# bleumaus-nrf52832-mk-1_0_0.net
KiCad netlist of a schematic drawn in EAGLE
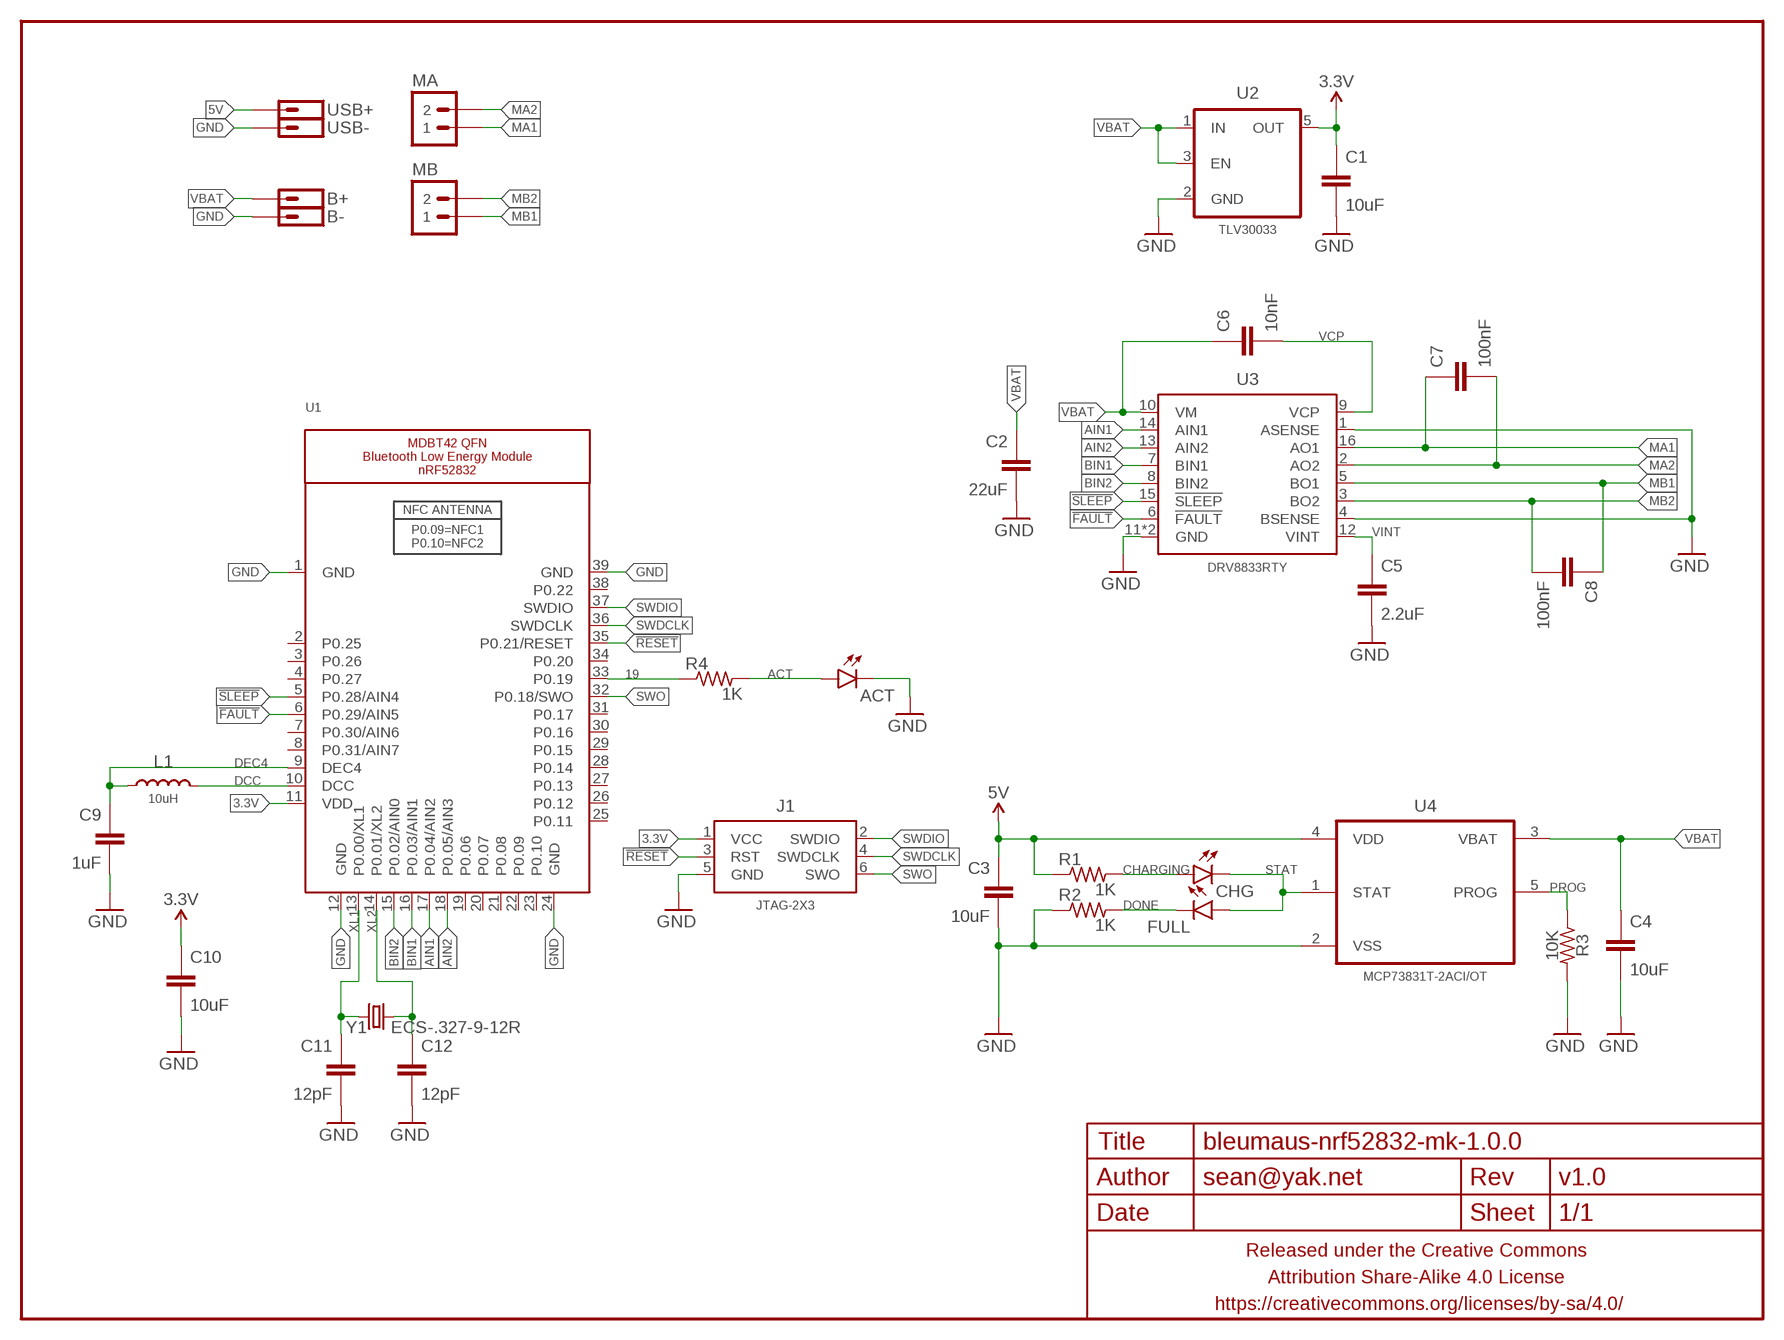
[diagram p0: schematic, sheet 1]

(export (version "E")
  (design (tool "Eeschema 10.0.6"))
  (components
    (comp (ref "ACT")
      (value "LED0603-TIGHT")
      (footprint "eagle-import:LED-0603-TIGHT")
      (libsource (lib "eagle-import") (part "LED0603-TIGHT"))
    )
    (comp (ref "B+")
      (value "M01SMD-1DIA")
      (footprint "eagle-import:1X01-SMD-1MM-DIA")
      (libsource (lib "eagle-import") (part "M01SMD-1DIA"))
    )
    (comp (ref "B-")
      (value "M01SMD-1DIA")
      (footprint "eagle-import:1X01-SMD-1MM-DIA")
      (libsource (lib "eagle-import") (part "M01SMD-1DIA"))
    )
    (comp (ref "C1")
      (value "10uF")
      (footprint "eagle-import:C0402")
      (libsource (lib "eagle-import") (part "CAPACITOR-CERAMICC0402"))
    )
    (comp (ref "C2")
      (value "22uF")
      (footprint "eagle-import:C1206")
      (libsource (lib "eagle-import") (part "CAPACITOR-CERAMICC1206"))
    )
    (comp (ref "C3")
      (value "10uF")
      (footprint "eagle-import:C0402")
      (libsource (lib "eagle-import") (part "CAPACITOR-CERAMICC0402"))
    )
    (comp (ref "C4")
      (value "10uF")
      (footprint "eagle-import:C0402")
      (libsource (lib "eagle-import") (part "CAPACITOR-CERAMICC0402"))
    )
    (comp (ref "C5")
      (value "2.2uF")
      (footprint "eagle-import:C0402")
      (libsource (lib "eagle-import") (part "CAPACITOR-CERAMICC0402"))
    )
    (comp (ref "C6")
      (value "10nF")
      (footprint "eagle-import:C0402")
      (libsource (lib "eagle-import") (part "CAPACITOR-CERAMICC0402"))
    )
    (comp (ref "C7")
      (value "100nF")
      (footprint "eagle-import:C0402")
      (libsource (lib "eagle-import") (part "CAPACITOR-CERAMICC0402"))
    )
    (comp (ref "C8")
      (value "100nF")
      (footprint "eagle-import:C0402")
      (libsource (lib "eagle-import") (part "CAPACITOR-CERAMICC0402"))
    )
    (comp (ref "C9")
      (value "1uF")
      (footprint "eagle-import:C0402")
      (libsource (lib "eagle-import") (part "CAPACITOR-CERAMICC0402"))
    )
    (comp (ref "C10")
      (value "10uF")
      (footprint "eagle-import:C0603-TIGHTER")
      (libsource (lib "eagle-import") (part "CAPACITOR-CERAMICC0603-TIGHTER"))
    )
    (comp (ref "C11")
      (value "12pF")
      (footprint "eagle-import:C0402")
      (libsource (lib "eagle-import") (part "CAPACITOR-CERAMICC0402"))
    )
    (comp (ref "C12")
      (value "12pF")
      (footprint "eagle-import:C0402")
      (libsource (lib "eagle-import") (part "CAPACITOR-CERAMICC0402"))
    )
    (comp (ref "CHG")
      (value "LED0603-TIGHT")
      (footprint "eagle-import:LED-0603-TIGHT")
      (libsource (lib "eagle-import") (part "LED0603-TIGHT"))
    )
    (comp (ref "FRAME1")
      (value "FRAME-LETTERNO_PACKAGE")
      (footprint "eagle-import:DUMMY")
      (fields
        (field (name "DESIGNER") "sean@yak.net")
        (field (name "VERSION") "v1.0")
        (field (name "DESIGNER_1") "sean@yak.net")
        (field (name "VERSION_1") "v1.0")
      )
      (libsource (lib "eagle-import") (part "FRAME-LETTERNO_PACKAGE"))
    )
    (comp (ref "FULL")
      (value "LED0603-TIGHT")
      (footprint "eagle-import:LED-0603-TIGHT")
      (libsource (lib "eagle-import") (part "LED0603-TIGHT"))
    )
    (comp (ref "J1")
      (value "JTAG-2X3")
      (footprint "eagle-import:2X3-1.27MM-SMD")
      (libsource (lib "eagle-import") (part "JTAG-2X3"))
    )
    (comp (ref "L1")
      (value "10uH")
      (footprint "eagle-import:0603")
      (libsource (lib "eagle-import") (part "INDUCTOR0603"))
    )
    (comp (ref "MA")
      (value "M02PTH-2MM")
      (footprint "eagle-import:1X02-2MM-PTH")
      (libsource (lib "eagle-import") (part "M02PTH-2MM"))
    )
    (comp (ref "MB")
      (value "M02PTH-2MM")
      (footprint "eagle-import:1X02-2MM-PTH")
      (libsource (lib "eagle-import") (part "M02PTH-2MM"))
    )
    (comp (ref "R1")
      (value "1K")
      (footprint "eagle-import:R0402")
      (libsource (lib "eagle-import") (part "RESISTORR0402"))
    )
    (comp (ref "R2")
      (value "1K")
      (footprint "eagle-import:R0402")
      (libsource (lib "eagle-import") (part "RESISTORR0402"))
    )
    (comp (ref "R3")
      (value "10K")
      (footprint "eagle-import:R0402")
      (libsource (lib "eagle-import") (part "RESISTORR0402"))
    )
    (comp (ref "R4")
      (value "1K")
      (footprint "eagle-import:R0402")
      (libsource (lib "eagle-import") (part "RESISTORR0402"))
    )
    (comp (ref "U1")
      (value "NRF52832_MODULE_MDBT42_NO2324")
      (footprint "eagle-import:BLE_MODULE_RAYTAC_MDBT42_NO2324")
      (libsource (lib "eagle-import") (part "NRF52832_MODULE_MDBT42_NO2324"))
    )
    (comp (ref "U2")
      (value "TLV30033")
      (footprint "eagle-import:SC70-TIGHTER")
      (libsource (lib "eagle-import") (part "V_REG_ENTLV700XXDCK-TIGHTER"))
    )
    (comp (ref "U3")
      (value "DRV8833RTY")
      (footprint "eagle-import:PWQFN-16")
      (libsource (lib "eagle-import") (part "DRV8833RTY"))
    )
    (comp (ref "U4")
      (value "MCP73831T-2ACI/OT")
      (footprint "eagle-import:SOT95P280X145-5N")
      (libsource (lib "eagle-import") (part "MCP73831T-2ACI/OT"))
    )
    (comp (ref "USB+")
      (value "M01SMD-1DIA")
      (footprint "eagle-import:1X01-SMD-1MM-DIA")
      (libsource (lib "eagle-import") (part "M01SMD-1DIA"))
    )
    (comp (ref "USB-")
      (value "M01SMD-1DIA")
      (footprint "eagle-import:1X01-SMD-1MM-DIA")
      (libsource (lib "eagle-import") (part "M01SMD-1DIA"))
    )
    (comp (ref "Y1")
      (value "ECS-.327-9-12R")
      (footprint "eagle-import:CRYSTAL-2X1.2MM")
      (libsource (lib "eagle-import") (part "CRYSTAL2X1.2MM"))
    )
  )
  (nets
    (net (code "1") (name "/19") (class "Default")
      (node (ref "R4") (pin "1") (pinfunction "1_1") (pintype "passive"))
      (node (ref "U1") (pin "33") (pinfunction "P0.19_33") (pintype "bidirectional"))
    )
    (net (code "2") (name "/ACT") (class "Default")
      (node (ref "ACT") (pin "A") (pinfunction "A_A") (pintype "passive"))
      (node (ref "R4") (pin "2") (pinfunction "2_2") (pintype "passive"))
    )
    (net (code "3") (name "/CHARGING") (class "Default")
      (node (ref "CHG") (pin "A") (pinfunction "A_A") (pintype "passive"))
      (node (ref "R1") (pin "2") (pinfunction "2_2") (pintype "passive"))
    )
    (net (code "4") (name "/DCC") (class "Default")
      (node (ref "L1") (pin "2") (pinfunction "2_2") (pintype "passive"))
      (node (ref "U1") (pin "10") (pinfunction "DCC_10") (pintype "bidirectional"))
    )
    (net (code "5") (name "/DEC4") (class "Default")
      (node (ref "C9") (pin "1") (pinfunction "1_1") (pintype "passive"))
      (node (ref "L1") (pin "1") (pinfunction "1_1") (pintype "passive"))
      (node (ref "U1") (pin "9") (pinfunction "DEC4_9") (pintype "bidirectional"))
    )
    (net (code "6") (name "/DONE") (class "Default")
      (node (ref "FULL") (pin "C") (pinfunction "C_C") (pintype "passive"))
      (node (ref "R2") (pin "2") (pinfunction "2_2") (pintype "passive"))
    )
    (net (code "7") (name "/PROG") (class "Default")
      (node (ref "R3") (pin "1") (pinfunction "1_1") (pintype "passive"))
      (node (ref "U4") (pin "5") (pinfunction "PROG_5") (pintype "input"))
    )
    (net (code "8") (name "/STAT") (class "Default")
      (node (ref "CHG") (pin "C") (pinfunction "C_C") (pintype "passive"))
      (node (ref "FULL") (pin "A") (pinfunction "A_A") (pintype "passive"))
      (node (ref "U4") (pin "1") (pinfunction "STAT_1") (pintype "output"))
    )
    (net (code "9") (name "/VCP") (class "Default")
      (node (ref "C6") (pin "2") (pinfunction "2_2") (pintype "passive"))
      (node (ref "U3") (pin "9") (pinfunction "VCP_9") (pintype "bidirectional"))
    )
    (net (code "10") (name "/VINT") (class "Default")
      (node (ref "C5") (pin "1") (pinfunction "1_1") (pintype "passive"))
      (node (ref "U3") (pin "12") (pinfunction "VINT_12") (pintype "bidirectional"))
    )
    (net (code "11") (name "/XL1") (class "Default")
      (node (ref "C11") (pin "1") (pinfunction "1_1") (pintype "passive"))
      (node (ref "U1") (pin "13") (pinfunction "P0.00/XL1_13") (pintype "bidirectional"))
      (node (ref "Y1") (pin "1") (pinfunction "1_1") (pintype "passive"))
    )
    (net (code "12") (name "/XL2") (class "Default")
      (node (ref "C12") (pin "1") (pinfunction "1_1") (pintype "passive"))
      (node (ref "U1") (pin "14") (pinfunction "P0.01/XL2_14") (pintype "bidirectional"))
      (node (ref "Y1") (pin "2") (pinfunction "2_2") (pintype "passive"))
    )
    (net (code "13") (name "/~{FAULT}") (class "Default")
      (node (ref "U1") (pin "6") (pinfunction "P0.29/AIN5_6") (pintype "bidirectional"))
      (node (ref "U3") (pin "6") (pinfunction "~{FAULT}_6") (pintype "output"))
    )
    (net (code "14") (name "/~{RESET}") (class "Default")
      (node (ref "J1") (pin "3") (pinfunction "RST_3") (pintype "bidirectional"))
      (node (ref "U1") (pin "35") (pinfunction "P0.21/RESET_35") (pintype "bidirectional"))
    )
    (net (code "15") (name "/~{SLEEP}") (class "Default")
      (node (ref "U1") (pin "5") (pinfunction "P0.28/AIN4_5") (pintype "bidirectional"))
      (node (ref "U3") (pin "15") (pinfunction "~{SLEEP}_15") (pintype "input"))
    )
    (net (code "16") (name "3.3V") (class "Default")
      (node (ref "C1") (pin "1") (pinfunction "1_1") (pintype "passive"))
      (node (ref "C10") (pin "1") (pinfunction "1_1") (pintype "passive"))
      (node (ref "J1") (pin "1") (pinfunction "VCC_1") (pintype "bidirectional"))
      (node (ref "U1") (pin "11") (pinfunction "VDD_11") (pintype "bidirectional"))
      (node (ref "U2") (pin "5") (pinfunction "OUT_5") (pintype "passive"))
    )
    (net (code "17") (name "5V") (class "Default")
      (node (ref "C3") (pin "1") (pinfunction "1_1") (pintype "passive"))
      (node (ref "R1") (pin "1") (pinfunction "1_1") (pintype "passive"))
      (node (ref "U4") (pin "4") (pinfunction "VDD_4") (pintype "power_in"))
      (node (ref "USB+") (pin "P$1") (pinfunction "1_P$1") (pintype "passive"))
    )
    (net (code "18") (name "AIN1") (class "Default")
      (node (ref "U1") (pin "17") (pinfunction "P0.04/AIN2_17") (pintype "bidirectional"))
      (node (ref "U3") (pin "14") (pinfunction "AIN1_14") (pintype "input"))
    )
    (net (code "19") (name "AIN2") (class "Default")
      (node (ref "U1") (pin "18") (pinfunction "P0.05/AIN3_18") (pintype "bidirectional"))
      (node (ref "U3") (pin "13") (pinfunction "AIN2_13") (pintype "input"))
    )
    (net (code "20") (name "BIN1") (class "Default")
      (node (ref "U1") (pin "16") (pinfunction "P0.03/AIN1_16") (pintype "bidirectional"))
      (node (ref "U3") (pin "7") (pinfunction "BIN1_7") (pintype "input"))
    )
    (net (code "21") (name "BIN2") (class "Default")
      (node (ref "U1") (pin "15") (pinfunction "P0.02/AIN0_15") (pintype "bidirectional"))
      (node (ref "U3") (pin "8") (pinfunction "BIN2_8") (pintype "input"))
    )
    (net (code "22") (name "GND") (class "Default")
      (node (ref "ACT") (pin "C") (pinfunction "C_C") (pintype "passive"))
      (node (ref "B-") (pin "P$1") (pinfunction "1_P$1") (pintype "passive"))
      (node (ref "C1") (pin "2") (pinfunction "2_2") (pintype "passive"))
      (node (ref "C10") (pin "2") (pinfunction "2_2") (pintype "passive"))
      (node (ref "C11") (pin "2") (pinfunction "2_2") (pintype "passive"))
      (node (ref "C12") (pin "2") (pinfunction "2_2") (pintype "passive"))
      (node (ref "C2") (pin "2") (pinfunction "2_2") (pintype "passive"))
      (node (ref "C3") (pin "2") (pinfunction "2_2") (pintype "passive"))
      (node (ref "C4") (pin "2") (pinfunction "2_2") (pintype "passive"))
      (node (ref "C5") (pin "2") (pinfunction "2_2") (pintype "passive"))
      (node (ref "C9") (pin "2") (pinfunction "2_2") (pintype "passive"))
      (node (ref "J1") (pin "5") (pinfunction "GND_5") (pintype "bidirectional"))
      (node (ref "R2") (pin "1") (pinfunction "1_1") (pintype "passive"))
      (node (ref "R3") (pin "2") (pinfunction "2_2") (pintype "passive"))
      (node (ref "U1") (pin "1") (pinfunction "GND_1") (pintype "bidirectional"))
      (node (ref "U1") (pin "12") (pinfunction "GND_12") (pintype "bidirectional"))
      (node (ref "U1") (pin "24") (pinfunction "GND_24") (pintype "bidirectional"))
      (node (ref "U1") (pin "39") (pinfunction "GND_39") (pintype "bidirectional"))
      (node (ref "U2") (pin "2") (pinfunction "GND_2") (pintype "input"))
      (node (ref "U3") (pin "1") (pinfunction "ASENSE_1") (pintype "bidirectional"))
      (node (ref "U3") (pin "11") (pinfunction "GND_11") (pintype "bidirectional"))
      (node (ref "U3") (pin "17") (pinfunction "GND_17") (pintype "bidirectional"))
      (node (ref "U3") (pin "4") (pinfunction "BSENSE_4") (pintype "bidirectional"))
      (node (ref "U4") (pin "2") (pinfunction "VSS_2") (pintype "power_in"))
      (node (ref "USB-") (pin "P$1") (pinfunction "1_P$1") (pintype "passive"))
    )
    (net (code "23") (name "MA1") (class "Default")
      (node (ref "C7") (pin "1") (pinfunction "1_1") (pintype "passive"))
      (node (ref "MA") (pin "P$1") (pinfunction "1_P$1") (pintype "passive"))
      (node (ref "U3") (pin "16") (pinfunction "AO1_16") (pintype "bidirectional"))
    )
    (net (code "24") (name "MA2") (class "Default")
      (node (ref "C7") (pin "2") (pinfunction "2_2") (pintype "passive"))
      (node (ref "MA") (pin "P$2") (pinfunction "2_P$2") (pintype "passive"))
      (node (ref "U3") (pin "2") (pinfunction "AO2_2") (pintype "bidirectional"))
    )
    (net (code "25") (name "MB1") (class "Default")
      (node (ref "C8") (pin "1") (pinfunction "1_1") (pintype "passive"))
      (node (ref "MB") (pin "P$1") (pinfunction "1_P$1") (pintype "passive"))
      (node (ref "U3") (pin "5") (pinfunction "BO1_5") (pintype "bidirectional"))
    )
    (net (code "26") (name "MB2") (class "Default")
      (node (ref "C8") (pin "2") (pinfunction "2_2") (pintype "passive"))
      (node (ref "MB") (pin "P$2") (pinfunction "2_P$2") (pintype "passive"))
      (node (ref "U3") (pin "3") (pinfunction "BO2_3") (pintype "bidirectional"))
    )
    (net (code "27") (name "SWDCLK") (class "Default")
      (node (ref "J1") (pin "4") (pinfunction "SWDCLK_4") (pintype "bidirectional"))
      (node (ref "U1") (pin "36") (pinfunction "SWDCLK_36") (pintype "bidirectional"))
    )
    (net (code "28") (name "SWDIO") (class "Default")
      (node (ref "J1") (pin "2") (pinfunction "SWDIO_2") (pintype "bidirectional"))
      (node (ref "U1") (pin "37") (pinfunction "SWDIO_37") (pintype "bidirectional"))
    )
    (net (code "29") (name "SWO") (class "Default")
      (node (ref "J1") (pin "6") (pinfunction "SWO_6") (pintype "bidirectional"))
      (node (ref "U1") (pin "32") (pinfunction "P0.18/SWO_32") (pintype "bidirectional"))
    )
    (net (code "30") (name "VBAT") (class "Default")
      (node (ref "B+") (pin "P$1") (pinfunction "1_P$1") (pintype "passive"))
      (node (ref "C2") (pin "1") (pinfunction "1_1") (pintype "passive"))
      (node (ref "C4") (pin "1") (pinfunction "1_1") (pintype "passive"))
      (node (ref "C6") (pin "1") (pinfunction "1_1") (pintype "passive"))
      (node (ref "U2") (pin "1") (pinfunction "IN_1") (pintype "input"))
      (node (ref "U2") (pin "3") (pinfunction "EN_3") (pintype "input"))
      (node (ref "U3") (pin "10") (pinfunction "VM_10") (pintype "bidirectional"))
      (node (ref "U4") (pin "3") (pinfunction "VBAT_3") (pintype "output"))
    )
    (net (code "31") (name "unconnected-(U1-P0.06-Pad19)") (class "Default")
      (node (ref "U1") (pin "19") (pinfunction "P0.06_19") (pintype "bidirectional"))
    )
    (net (code "32") (name "unconnected-(U1-P0.07-Pad20)") (class "Default")
      (node (ref "U1") (pin "20") (pinfunction "P0.07_20") (pintype "bidirectional"))
    )
    (net (code "33") (name "unconnected-(U1-P0.08-Pad21)") (class "Default")
      (node (ref "U1") (pin "21") (pinfunction "P0.08_21") (pintype "bidirectional"))
    )
    (net (code "34") (name "unconnected-(U1-P0.09-Pad22)") (class "Default")
      (node (ref "U1") (pin "22") (pinfunction "P0.09_22") (pintype "bidirectional"))
    )
    (net (code "35") (name "unconnected-(U1-P0.10-Pad23)") (class "Default")
      (node (ref "U1") (pin "23") (pinfunction "P0.10_23") (pintype "bidirectional"))
    )
    (net (code "36") (name "unconnected-(U1-P0.11-Pad25)") (class "Default")
      (node (ref "U1") (pin "25") (pinfunction "P0.11_25") (pintype "bidirectional"))
    )
    (net (code "37") (name "unconnected-(U1-P0.12-Pad26)") (class "Default")
      (node (ref "U1") (pin "26") (pinfunction "P0.12_26") (pintype "bidirectional"))
    )
    (net (code "38") (name "unconnected-(U1-P0.13-Pad27)") (class "Default")
      (node (ref "U1") (pin "27") (pinfunction "P0.13_27") (pintype "bidirectional"))
    )
    (net (code "39") (name "unconnected-(U1-P0.14-Pad28)") (class "Default")
      (node (ref "U1") (pin "28") (pinfunction "P0.14_28") (pintype "bidirectional"))
    )
    (net (code "40") (name "unconnected-(U1-P0.15-Pad29)") (class "Default")
      (node (ref "U1") (pin "29") (pinfunction "P0.15_29") (pintype "bidirectional"))
    )
    (net (code "41") (name "unconnected-(U1-P0.16-Pad30)") (class "Default")
      (node (ref "U1") (pin "30") (pinfunction "P0.16_30") (pintype "bidirectional"))
    )
    (net (code "42") (name "unconnected-(U1-P0.17-Pad31)") (class "Default")
      (node (ref "U1") (pin "31") (pinfunction "P0.17_31") (pintype "bidirectional"))
    )
    (net (code "43") (name "unconnected-(U1-P0.20-Pad34)") (class "Default")
      (node (ref "U1") (pin "34") (pinfunction "P0.20_34") (pintype "bidirectional"))
    )
    (net (code "44") (name "unconnected-(U1-P0.22-Pad38)") (class "Default")
      (node (ref "U1") (pin "38") (pinfunction "P0.22_38") (pintype "bidirectional"))
    )
    (net (code "45") (name "unconnected-(U1-P0.25-Pad2)") (class "Default")
      (node (ref "U1") (pin "2") (pinfunction "P0.25_2") (pintype "bidirectional"))
    )
    (net (code "46") (name "unconnected-(U1-P0.26-Pad3)") (class "Default")
      (node (ref "U1") (pin "3") (pinfunction "P0.26_3") (pintype "bidirectional"))
    )
    (net (code "47") (name "unconnected-(U1-P0.27-Pad4)") (class "Default")
      (node (ref "U1") (pin "4") (pinfunction "P0.27_4") (pintype "bidirectional"))
    )
    (net (code "48") (name "unconnected-(U1-P0.30{slash}AIN6-Pad7)") (class "Default")
      (node (ref "U1") (pin "7") (pinfunction "P0.30/AIN6_7") (pintype "bidirectional"))
    )
    (net (code "49") (name "unconnected-(U1-P0.31{slash}AIN7-Pad8)") (class "Default")
      (node (ref "U1") (pin "8") (pinfunction "P0.31/AIN7_8") (pintype "bidirectional"))
    )
  )
)
